# 03_CAN.net
KiCad netlist of a schematic drawn in Altium Designer
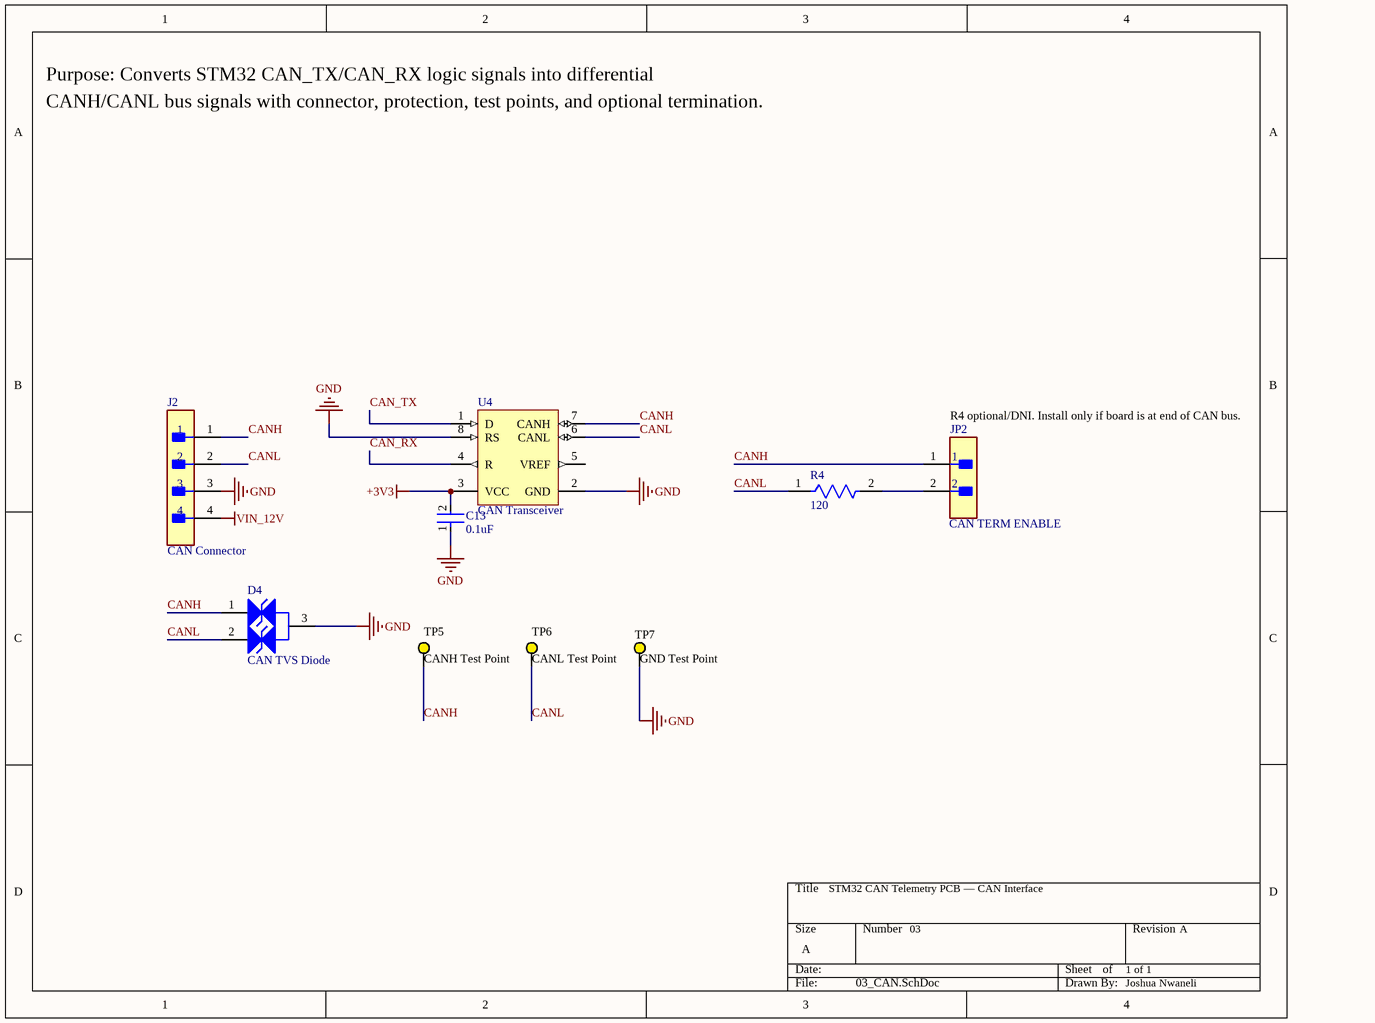
[diagram p0: 03_CAN.SchDoc]

(export (version "E")
  (design (tool "Eeschema 10.0.6"))
  (components
    (comp (ref "C13")
      (value "0.1uF")
      (footprint "FP-CC0805-EB-MFG")
      (description "CC0805KKX7RYBB104 Capacitor Ceramic 0.01uF 250V X7R 10% 0805 T/R")
      (fields (field (name "TOLERANCE") "10%"))
      (libsource (lib "Altium Content Vault") (part "b4654b650e69147ec39a6b967a45e02"))
    )
    (comp (ref "D4")
      (value "CAN TVS Diode")
      (footprint "ONSC-SOT-23-3-318-08_V")
      (description "Dual-line ESD/transient protection for CANH and CANL")
      (fields (field (name "MANUFACTURER") "On Semiconductor") (field (name "PARTNUMBER") "SZNUP2105LT3G"))
      (libsource (lib "Altium Content Vault") (part "ONSC-NUP21X5X-SOT-23-3-318-08"))
    )
    (comp (ref "J2")
      (value "CAN Connector")
      (footprint "FP-1777099-MFG")
      (description "TERM BLOCK HDR 4POS VERT 5.08MM")
      (fields (field (name "VOLTAGE") "300V"))
      (libsource (lib "Altium Content Vault") (part "299a8cea1bdcbc3624fe62c390fa72c"))
    )
    (comp (ref "JP2")
      (value "CAN TERM ENABLE")
      (footprint "FP-TSW-102-12-T-S-MFG")
      (description "Jumper to enable optional 120R CAN bus termination")
      (libsource (lib "Altium Content Vault") (part "3bc925449376181038e59eaffc5286c"))
    )
    (comp (ref "R4")
      (value "120")
      (footprint "FP-RT0805-MFG")
      (description "RT0805 120Ω 0.125W 25 ppm/°C 1.00%")
      (fields (field (name "OCTOPART") "https://octopart.com/rt0805drd07120rl-yageo-1204488"))
      (libsource (lib "Altium Content Vault") (part "1029c3af85768c4190bb7ad29bc67b5"))
    )
    (comp (ref "TP5")
      (value "CANH Test Point")
      (footprint "KSTN-5014_V")
      (description "Test Point, Yellow, Through Hole, RoHS, Bulk")
      (fields (field (name "MANUFACTURER") "Keystone"))
      (libsource (lib "Altium Content Vault") (part "TESTPOINT_YELLOW"))
    )
    (comp (ref "TP6")
      (value "CANL Test Point")
      (footprint "KSTN-5014_V")
      (description "Test Point, Yellow, Through Hole, RoHS, Bulk")
      (fields (field (name "MANUFACTURER") "Keystone"))
      (libsource (lib "Altium Content Vault") (part "TESTPOINT_YELLOW"))
    )
    (comp (ref "TP7")
      (value "GND Test Point")
      (footprint "KSTN-5014_V")
      (description "Test Point, Yellow, Through Hole, RoHS, Bulk")
      (fields (field (name "MANUFACTURER") "Keystone"))
      (libsource (lib "Altium Content Vault") (part "TESTPOINT_YELLOW"))
    )
    (comp (ref "U4")
      (value "CAN Transceiver")
      (footprint "D0008A_M")
      (description "CAN Bus Transceiver, 3.3 V, -40 to 85 degC, 8-Pin SOIC (D), Green (RoHS & no Sb/Br), Tube")
      (fields (field (name "PARTNUMBER") "SN65HVD230D") (field (name "GENERIC PART NUMBER") "SN65HVD230"))
      (libsource (lib "Altium Content Vault") (part "TI-SN65HVD230D-SOIC_D-8"))
    )
  )
  (nets
    (net (code "1") (name "+3V3") (class "Default")
      (node (ref "C13") (pin "2") (pinfunction "2_2") (pintype "passive"))
      (node (ref "U4") (pin "3") (pinfunction "VCC_3") (pintype "power_in"))
    )
    (net (code "2") (name "/CANH") (class "Default")
      (node (ref "D4") (pin "1") (pinfunction "K_1") (pintype "passive"))
      (node (ref "J2") (pin "1") (pinfunction "1_1") (pintype "passive"))
      (node (ref "JP2") (pin "1") (pinfunction "1_1") (pintype "passive"))
      (node (ref "TP5") (pin "1") (pinfunction "1_1") (pintype "passive"))
      (node (ref "U4") (pin "7") (pinfunction "CANH_7") (pintype "bidirectional"))
    )
    (net (code "3") (name "/CANL") (class "Default")
      (node (ref "D4") (pin "2") (pinfunction "K_2") (pintype "passive"))
      (node (ref "J2") (pin "2") (pinfunction "2_2") (pintype "passive"))
      (node (ref "R4") (pin "1") (pinfunction "1_1") (pintype "passive"))
      (node (ref "TP6") (pin "1") (pinfunction "1_1") (pintype "passive"))
      (node (ref "U4") (pin "6") (pinfunction "CANL_6") (pintype "bidirectional"))
    )
    (net (code "4") (name "/CAN_RX") (class "Default")
      (node (ref "U4") (pin "4") (pinfunction "R_4") (pintype "output"))
    )
    (net (code "5") (name "/CAN_TX") (class "Default")
      (node (ref "U4") (pin "1") (pinfunction "D_1") (pintype "input"))
    )
    (net (code "6") (name "GND") (class "Default")
      (node (ref "C13") (pin "1") (pinfunction "1_1") (pintype "passive"))
      (node (ref "D4") (pin "3") (pinfunction "K_3") (pintype "passive"))
      (node (ref "J2") (pin "3") (pinfunction "3_3") (pintype "passive"))
      (node (ref "TP7") (pin "1") (pinfunction "1_1") (pintype "passive"))
      (node (ref "U4") (pin "2") (pinfunction "GND_2") (pintype "power_in"))
      (node (ref "U4") (pin "8") (pinfunction "RS_8") (pintype "input"))
    )
    (net (code "7") (name "Net-(JP2-Pad2)") (class "Default")
      (node (ref "JP2") (pin "2") (pinfunction "2_2") (pintype "passive"))
      (node (ref "R4") (pin "2") (pinfunction "2_2") (pintype "passive"))
    )
    (net (code "8") (name "VIN_12V") (class "Default")
      (node (ref "J2") (pin "4") (pinfunction "4_4") (pintype "passive"))
    )
    (net (code "9") (name "unconnected-(U4-VREF-Pad5)") (class "Default")
      (node (ref "U4") (pin "5") (pinfunction "VREF_5") (pintype "output"))
    )
  )
)
